# tube_clock_shield_v1.net
KiCad netlist of a schematic drawn in EAGLE
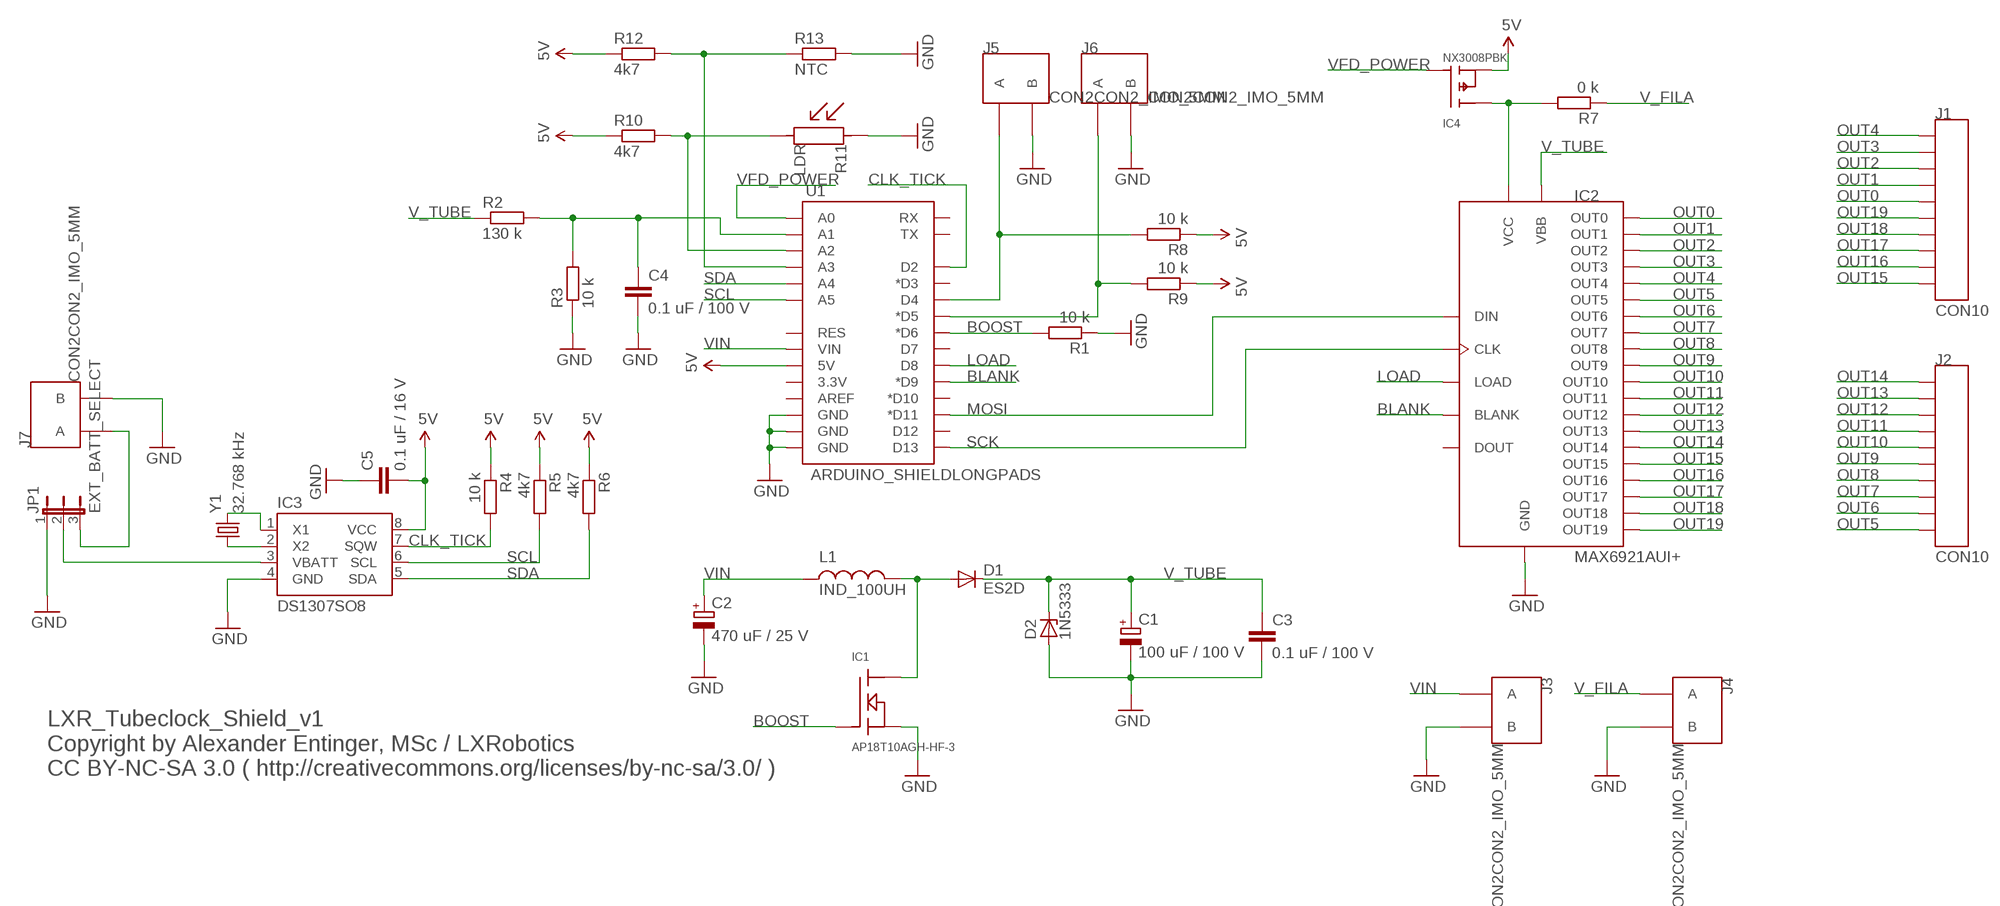
[diagram p0: schematic, sheet 1]

(export (version "E")
  (design (tool "Eeschema 10.0.6"))
  (components
    (comp (ref "C1")
      (value "100 uF / 100 V")
      (footprint "eagle-import:E5-10,5")
      (libsource (lib "eagle-import") (part "CPOL-EUE5-10.5"))
    )
    (comp (ref "C2")
      (value "470 uF / 25 V")
      (footprint "eagle-import:E5-10,5")
      (libsource (lib "eagle-import") (part "CPOL-EUE5-10.5"))
    )
    (comp (ref "C3")
      (value "0.1 uF / 100 V")
      (footprint "eagle-import:C0805")
      (libsource (lib "eagle-import") (part "C-EUC0805"))
    )
    (comp (ref "C4")
      (value "0.1 uF / 100 V")
      (footprint "eagle-import:C0805")
      (libsource (lib "eagle-import") (part "C-EUC0805"))
    )
    (comp (ref "C5")
      (value "0.1 uF / 16 V")
      (footprint "eagle-import:C0805")
      (libsource (lib "eagle-import") (part "C-EUC0805"))
    )
    (comp (ref "D1")
      (value "ES2D")
      (footprint "eagle-import:SMB")
      (libsource (lib "eagle-import") (part "ES2D"))
    )
    (comp (ref "D2")
      (value "1N5333")
      (footprint "eagle-import:C1702-15")
      (libsource (lib "eagle-import") (part "1N5333"))
    )
    (comp (ref "IC1")
      (value "AP18T10AGH-HF-3")
      (footprint "eagle-import:TO252")
      (libsource (lib "eagle-import") (part "AP18T10AGH-HF-3"))
    )
    (comp (ref "IC2")
      (value "MAX6921AUI+")
      (footprint "eagle-import:TSSOP28")
      (libsource (lib "eagle-import") (part "MAX6921AUI+"))
    )
    (comp (ref "IC3")
      (value "DS1307SO8")
      (footprint "eagle-import:SO08")
      (libsource (lib "eagle-import") (part "DS1307SO8"))
    )
    (comp (ref "IC4")
      (value "NX3008PBK")
      (footprint "eagle-import:SOT23")
      (libsource (lib "eagle-import") (part "NX3008PBK"))
    )
    (comp (ref "J1")
      (value "CON10")
      (footprint "eagle-import:CON10")
      (libsource (lib "eagle-import") (part "CON10"))
    )
    (comp (ref "J2")
      (value "CON10")
      (footprint "eagle-import:CON10")
      (libsource (lib "eagle-import") (part "CON10"))
    )
    (comp (ref "J3")
      (value "CON2CON2_IMO_5MM")
      (footprint "eagle-import:CON2_IMO")
      (libsource (lib "eagle-import") (part "CON2CON2_IMO_5MM"))
    )
    (comp (ref "J4")
      (value "CON2CON2_IMO_5MM")
      (footprint "eagle-import:CON2_IMO")
      (libsource (lib "eagle-import") (part "CON2CON2_IMO_5MM"))
    )
    (comp (ref "J5")
      (value "CON2CON2_IMO_5MM")
      (footprint "eagle-import:CON2_IMO")
      (libsource (lib "eagle-import") (part "CON2CON2_IMO_5MM"))
    )
    (comp (ref "J6")
      (value "CON2CON2_IMO_5MM")
      (footprint "eagle-import:CON2_IMO")
      (libsource (lib "eagle-import") (part "CON2CON2_IMO_5MM"))
    )
    (comp (ref "J7")
      (value "CON2CON2_IMO_5MM")
      (footprint "eagle-import:CON2_IMO")
      (libsource (lib "eagle-import") (part "CON2CON2_IMO_5MM"))
    )
    (comp (ref "JP1")
      (value "EXT_BATT_SELECT")
      (footprint "eagle-import:JP2")
      (libsource (lib "eagle-import") (part "JP2E"))
    )
    (comp (ref "L1")
      (value "IND_100UH")
      (footprint "eagle-import:LEISTUNGS_INDUKTIVITAET_PACKAGE")
      (libsource (lib "eagle-import") (part "IND_100UH"))
    )
    (comp (ref "R1")
      (value "10 k")
      (footprint "eagle-import:R0805")
      (libsource (lib "eagle-import") (part "R-EU_R0805"))
    )
    (comp (ref "R2")
      (value "130 k")
      (footprint "eagle-import:R0805")
      (libsource (lib "eagle-import") (part "R-EU_R0805"))
    )
    (comp (ref "R3")
      (value "10 k")
      (footprint "eagle-import:R0805")
      (libsource (lib "eagle-import") (part "R-EU_R0805"))
    )
    (comp (ref "R4")
      (value "10 k")
      (footprint "eagle-import:R0805")
      (libsource (lib "eagle-import") (part "R-EU_R0805"))
    )
    (comp (ref "R5")
      (value "4k7")
      (footprint "eagle-import:R0805")
      (libsource (lib "eagle-import") (part "R-EU_R0805"))
    )
    (comp (ref "R6")
      (value "4k7")
      (footprint "eagle-import:R0805")
      (libsource (lib "eagle-import") (part "R-EU_R0805"))
    )
    (comp (ref "R7")
      (value "0 k")
      (footprint "eagle-import:R0805")
      (libsource (lib "eagle-import") (part "R-EU_R0805"))
    )
    (comp (ref "R8")
      (value "10 k")
      (footprint "eagle-import:R0805")
      (libsource (lib "eagle-import") (part "R-EU_R0805"))
    )
    (comp (ref "R9")
      (value "10 k")
      (footprint "eagle-import:R0805")
      (libsource (lib "eagle-import") (part "R-EU_R0805"))
    )
    (comp (ref "R10")
      (value "4k7")
      (footprint "eagle-import:R0805")
      (libsource (lib "eagle-import") (part "R-EU_R0805"))
    )
    (comp (ref "R11")
      (value "LDR")
      (footprint "eagle-import:LDR")
      (libsource (lib "eagle-import") (part "LDR"))
    )
    (comp (ref "R12")
      (value "4k7")
      (footprint "eagle-import:R0805")
      (libsource (lib "eagle-import") (part "R-EU_R0805"))
    )
    (comp (ref "R13")
      (value "NTC")
      (footprint "eagle-import:R0805")
      (libsource (lib "eagle-import") (part "R-EU_R0805"))
    )
    (comp (ref "U1")
      (value "ARDUINO_SHIELDLONGPADS")
      (footprint "eagle-import:DUEMILANOVE_SHIELD_LONGPADS")
      (libsource (lib "eagle-import") (part "ARDUINO_SHIELDLONGPADS"))
    )
    (comp (ref "Y1")
      (value "32.768 kHz")
      (footprint "eagle-import:TC26HEZ")
      (libsource (lib "eagle-import") (part "CRYSTALTC26H_EZ"))
    )
  )
  (nets
    (net (code "1") (name "/BLANK") (class "Default")
      (node (ref "IC2") (pin "20") (pinfunction "BLANK_20") (pintype "bidirectional"))
      (node (ref "U1") (pin "D9") (pinfunction "*D9_D9") (pintype "bidirectional"))
    )
    (net (code "2") (name "/BOOST") (class "Default")
      (node (ref "IC1") (pin "G") (pinfunction "G_G") (pintype "bidirectional"))
      (node (ref "R1") (pin "2") (pinfunction "2_2") (pintype "passive"))
      (node (ref "U1") (pin "D6") (pinfunction "*D6_D6") (pintype "bidirectional"))
    )
    (net (code "3") (name "/CLK_TICK") (class "Default")
      (node (ref "IC3") (pin "7") (pinfunction "SQW_7") (pintype "bidirectional"))
      (node (ref "R4") (pin "2") (pinfunction "2_2") (pintype "passive"))
      (node (ref "U1") (pin "D2") (pinfunction "D2_D2") (pintype "bidirectional"))
    )
    (net (code "4") (name "/LOAD") (class "Default")
      (node (ref "IC2") (pin "23") (pinfunction "LOAD_23") (pintype "bidirectional"))
      (node (ref "U1") (pin "D8") (pinfunction "D8_D8") (pintype "bidirectional"))
    )
    (net (code "5") (name "/MOSI") (class "Default")
      (node (ref "IC2") (pin "6") (pinfunction "DIN_6") (pintype "bidirectional"))
      (node (ref "U1") (pin "D11") (pinfunction "*D11_D11") (pintype "bidirectional"))
    )
    (net (code "6") (name "/OUT0") (class "Default")
      (node (ref "IC2") (pin "5") (pinfunction "OUT0_5") (pintype "bidirectional"))
      (node (ref "J1") (pin "P$5") (pinfunction "P$5_P$5") (pintype "bidirectional"))
    )
    (net (code "7") (name "/OUT1") (class "Default")
      (node (ref "IC2") (pin "4") (pinfunction "OUT1_4") (pintype "bidirectional"))
      (node (ref "J1") (pin "P$4") (pinfunction "P$4_P$4") (pintype "bidirectional"))
    )
    (net (code "8") (name "/OUT2") (class "Default")
      (node (ref "IC2") (pin "3") (pinfunction "OUT2_3") (pintype "bidirectional"))
      (node (ref "J1") (pin "P$3") (pinfunction "P$3_P$3") (pintype "bidirectional"))
    )
    (net (code "9") (name "/OUT3") (class "Default")
      (node (ref "IC2") (pin "2") (pinfunction "OUT3_2") (pintype "bidirectional"))
      (node (ref "J1") (pin "P$2") (pinfunction "P$2_P$2") (pintype "bidirectional"))
    )
    (net (code "10") (name "/OUT4") (class "Default")
      (node (ref "IC2") (pin "1") (pinfunction "OUT4_1") (pintype "bidirectional"))
      (node (ref "J1") (pin "P$1") (pinfunction "P$1_P$1") (pintype "bidirectional"))
    )
    (net (code "11") (name "/OUT5") (class "Default")
      (node (ref "IC2") (pin "28") (pinfunction "OUT5_28") (pintype "bidirectional"))
      (node (ref "J2") (pin "P$10") (pinfunction "P$10_P$10") (pintype "bidirectional"))
    )
    (net (code "12") (name "/OUT6") (class "Default")
      (node (ref "IC2") (pin "27") (pinfunction "OUT6_27") (pintype "bidirectional"))
      (node (ref "J2") (pin "P$9") (pinfunction "P$9_P$9") (pintype "bidirectional"))
    )
    (net (code "13") (name "/OUT7") (class "Default")
      (node (ref "IC2") (pin "26") (pinfunction "OUT7_26") (pintype "bidirectional"))
      (node (ref "J2") (pin "P$8") (pinfunction "P$8_P$8") (pintype "bidirectional"))
    )
    (net (code "14") (name "/OUT8") (class "Default")
      (node (ref "IC2") (pin "25") (pinfunction "OUT8_25") (pintype "bidirectional"))
      (node (ref "J2") (pin "P$7") (pinfunction "P$7_P$7") (pintype "bidirectional"))
    )
    (net (code "15") (name "/OUT9") (class "Default")
      (node (ref "IC2") (pin "24") (pinfunction "OUT9_24") (pintype "bidirectional"))
      (node (ref "J2") (pin "P$6") (pinfunction "P$6_P$6") (pintype "bidirectional"))
    )
    (net (code "16") (name "/OUT10") (class "Default")
      (node (ref "IC2") (pin "19") (pinfunction "OUT10_19") (pintype "bidirectional"))
      (node (ref "J2") (pin "P$5") (pinfunction "P$5_P$5") (pintype "bidirectional"))
    )
    (net (code "17") (name "/OUT11") (class "Default")
      (node (ref "IC2") (pin "18") (pinfunction "OUT11_18") (pintype "bidirectional"))
      (node (ref "J2") (pin "P$4") (pinfunction "P$4_P$4") (pintype "bidirectional"))
    )
    (net (code "18") (name "/OUT12") (class "Default")
      (node (ref "IC2") (pin "17") (pinfunction "OUT12_17") (pintype "bidirectional"))
      (node (ref "J2") (pin "P$3") (pinfunction "P$3_P$3") (pintype "bidirectional"))
    )
    (net (code "19") (name "/OUT13") (class "Default")
      (node (ref "IC2") (pin "16") (pinfunction "OUT13_16") (pintype "bidirectional"))
      (node (ref "J2") (pin "P$2") (pinfunction "P$2_P$2") (pintype "bidirectional"))
    )
    (net (code "20") (name "/OUT14") (class "Default")
      (node (ref "IC2") (pin "15") (pinfunction "OUT14_15") (pintype "bidirectional"))
      (node (ref "J2") (pin "P$1") (pinfunction "P$1_P$1") (pintype "bidirectional"))
    )
    (net (code "21") (name "/OUT15") (class "Default")
      (node (ref "IC2") (pin "14") (pinfunction "OUT15_14") (pintype "bidirectional"))
      (node (ref "J1") (pin "P$10") (pinfunction "P$10_P$10") (pintype "bidirectional"))
    )
    (net (code "22") (name "/OUT16") (class "Default")
      (node (ref "IC2") (pin "13") (pinfunction "OUT16_13") (pintype "bidirectional"))
      (node (ref "J1") (pin "P$9") (pinfunction "P$9_P$9") (pintype "bidirectional"))
    )
    (net (code "23") (name "/OUT17") (class "Default")
      (node (ref "IC2") (pin "12") (pinfunction "OUT17_12") (pintype "bidirectional"))
      (node (ref "J1") (pin "P$8") (pinfunction "P$8_P$8") (pintype "bidirectional"))
    )
    (net (code "24") (name "/OUT18") (class "Default")
      (node (ref "IC2") (pin "11") (pinfunction "OUT18_11") (pintype "bidirectional"))
      (node (ref "J1") (pin "P$7") (pinfunction "P$7_P$7") (pintype "bidirectional"))
    )
    (net (code "25") (name "/OUT19") (class "Default")
      (node (ref "IC2") (pin "10") (pinfunction "OUT19_10") (pintype "bidirectional"))
      (node (ref "J1") (pin "P$6") (pinfunction "P$6_P$6") (pintype "bidirectional"))
    )
    (net (code "26") (name "/SCK") (class "Default")
      (node (ref "IC2") (pin "22") (pinfunction "CLK_22") (pintype "bidirectional"))
      (node (ref "U1") (pin "D13") (pinfunction "D13_D13") (pintype "bidirectional"))
    )
    (net (code "27") (name "/SCL") (class "Default")
      (node (ref "IC3") (pin "6") (pinfunction "SCL_6") (pintype "bidirectional"))
      (node (ref "R5") (pin "2") (pinfunction "2_2") (pintype "passive"))
      (node (ref "U1") (pin "A5") (pinfunction "A5_A5") (pintype "bidirectional"))
    )
    (net (code "28") (name "/SDA") (class "Default")
      (node (ref "IC3") (pin "5") (pinfunction "SDA_5") (pintype "bidirectional"))
      (node (ref "R6") (pin "2") (pinfunction "2_2") (pintype "passive"))
      (node (ref "U1") (pin "A4") (pinfunction "A4_A4") (pintype "bidirectional"))
    )
    (net (code "29") (name "/VFD_POWER") (class "Default")
      (node (ref "IC4") (pin "1") (pinfunction "G_1") (pintype "bidirectional"))
      (node (ref "U1") (pin "A0") (pinfunction "A0_A0") (pintype "bidirectional"))
    )
    (net (code "30") (name "/VIN") (class "Default")
      (node (ref "C2") (pin "+") (pinfunction "+_+") (pintype "passive"))
      (node (ref "J3") (pin "P$1") (pinfunction "A_P$1") (pintype "bidirectional"))
      (node (ref "L1") (pin "P$1") (pinfunction "P$1_P$1") (pintype "bidirectional"))
      (node (ref "U1") (pin "VIN") (pinfunction "VIN_VIN") (pintype "bidirectional"))
    )
    (net (code "31") (name "/V_FILA") (class "Default")
      (node (ref "J4") (pin "P$1") (pinfunction "A_P$1") (pintype "bidirectional"))
      (node (ref "R7") (pin "1") (pinfunction "1_1") (pintype "passive"))
    )
    (net (code "32") (name "/V_TUBE") (class "Default")
      (node (ref "C1") (pin "+") (pinfunction "+_+") (pintype "passive"))
      (node (ref "C3") (pin "1") (pinfunction "1_1") (pintype "passive"))
      (node (ref "D1") (pin "C") (pinfunction "C_C") (pintype "passive"))
      (node (ref "D2") (pin "C") (pinfunction "C_C") (pintype "passive"))
      (node (ref "IC2") (pin "8") (pinfunction "VBB_8") (pintype "bidirectional"))
      (node (ref "R2") (pin "1") (pinfunction "1_1") (pintype "passive"))
    )
    (net (code "33") (name "5V") (class "Default")
      (node (ref "C5") (pin "2") (pinfunction "2_2") (pintype "passive"))
      (node (ref "IC3") (pin "8") (pinfunction "VCC_8") (pintype "bidirectional"))
      (node (ref "IC4") (pin "2") (pinfunction "S_2") (pintype "bidirectional"))
      (node (ref "R10") (pin "1") (pinfunction "1_1") (pintype "passive"))
      (node (ref "R12") (pin "1") (pinfunction "1_1") (pintype "passive"))
      (node (ref "R4") (pin "1") (pinfunction "1_1") (pintype "passive"))
      (node (ref "R5") (pin "1") (pinfunction "1_1") (pintype "passive"))
      (node (ref "R6") (pin "1") (pinfunction "1_1") (pintype "passive"))
      (node (ref "R8") (pin "1") (pinfunction "1_1") (pintype "passive"))
      (node (ref "R9") (pin "1") (pinfunction "1_1") (pintype "passive"))
      (node (ref "U1") (pin "5V") (pinfunction "5V_5V") (pintype "bidirectional"))
    )
    (net (code "34") (name "GND") (class "Default")
      (node (ref "C1") (pin "-") (pinfunction "-_-") (pintype "passive"))
      (node (ref "C2") (pin "-") (pinfunction "-_-") (pintype "passive"))
      (node (ref "C3") (pin "2") (pinfunction "2_2") (pintype "passive"))
      (node (ref "C4") (pin "2") (pinfunction "2_2") (pintype "passive"))
      (node (ref "C5") (pin "1") (pinfunction "1_1") (pintype "passive"))
      (node (ref "D2") (pin "A") (pinfunction "A_A") (pintype "passive"))
      (node (ref "IC1") (pin "S") (pinfunction "S_S") (pintype "bidirectional"))
      (node (ref "IC2") (pin "21") (pinfunction "GND_21") (pintype "bidirectional"))
      (node (ref "IC3") (pin "4") (pinfunction "GND_4") (pintype "bidirectional"))
      (node (ref "J3") (pin "P$2") (pinfunction "B_P$2") (pintype "bidirectional"))
      (node (ref "J4") (pin "P$2") (pinfunction "B_P$2") (pintype "bidirectional"))
      (node (ref "J5") (pin "P$2") (pinfunction "B_P$2") (pintype "bidirectional"))
      (node (ref "J6") (pin "P$2") (pinfunction "B_P$2") (pintype "bidirectional"))
      (node (ref "J7") (pin "P$2") (pinfunction "B_P$2") (pintype "bidirectional"))
      (node (ref "JP1") (pin "1") (pinfunction "1_1") (pintype "passive"))
      (node (ref "R1") (pin "1") (pinfunction "1_1") (pintype "passive"))
      (node (ref "R11") (pin "P$1") (pinfunction "P$1_P$1") (pintype "bidirectional"))
      (node (ref "R13") (pin "2") (pinfunction "2_2") (pintype "passive"))
      (node (ref "R3") (pin "1") (pinfunction "1_1") (pintype "passive"))
      (node (ref "U1") (pin "GND@0") (pinfunction "GND_GND@0") (pintype "bidirectional"))
      (node (ref "U1") (pin "GND@1") (pinfunction "GND_GND@1") (pintype "bidirectional"))
      (node (ref "U1") (pin "GND@2") (pinfunction "GND_GND@2") (pintype "bidirectional"))
    )
    (net (code "35") (name "Net-(C4-Pad1)") (class "Default")
      (node (ref "C4") (pin "1") (pinfunction "1_1") (pintype "passive"))
      (node (ref "R2") (pin "2") (pinfunction "2_2") (pintype "passive"))
      (node (ref "R3") (pin "2") (pinfunction "2_2") (pintype "passive"))
      (node (ref "U1") (pin "A1") (pinfunction "A1_A1") (pintype "bidirectional"))
    )
    (net (code "36") (name "Net-(D1-PadA)") (class "Default")
      (node (ref "D1") (pin "A") (pinfunction "A_A") (pintype "passive"))
      (node (ref "IC1") (pin "D") (pinfunction "D_D") (pintype "bidirectional"))
      (node (ref "L1") (pin "P$2") (pinfunction "P$2_P$2") (pintype "bidirectional"))
    )
    (net (code "37") (name "Net-(IC2-VCC)") (class "Default")
      (node (ref "IC2") (pin "7") (pinfunction "VCC_7") (pintype "bidirectional"))
      (node (ref "IC4") (pin "3") (pinfunction "D_3") (pintype "bidirectional"))
      (node (ref "R7") (pin "2") (pinfunction "2_2") (pintype "passive"))
    )
    (net (code "38") (name "Net-(IC3-VBATT)") (class "Default")
      (node (ref "IC3") (pin "3") (pinfunction "VBATT_3") (pintype "bidirectional"))
      (node (ref "JP1") (pin "2") (pinfunction "2_2") (pintype "passive"))
    )
    (net (code "39") (name "Net-(IC3-X1)") (class "Default")
      (node (ref "IC3") (pin "1") (pinfunction "X1_1") (pintype "bidirectional"))
      (node (ref "Y1") (pin "2") (pinfunction "2_2") (pintype "passive"))
    )
    (net (code "40") (name "Net-(IC3-X2)") (class "Default")
      (node (ref "IC3") (pin "2") (pinfunction "X2_2") (pintype "bidirectional"))
      (node (ref "Y1") (pin "1") (pinfunction "1_1") (pintype "passive"))
    )
    (net (code "41") (name "Net-(J5-A)") (class "Default")
      (node (ref "J5") (pin "P$1") (pinfunction "A_P$1") (pintype "bidirectional"))
      (node (ref "R8") (pin "2") (pinfunction "2_2") (pintype "passive"))
      (node (ref "U1") (pin "D4") (pinfunction "D4_D4") (pintype "bidirectional"))
    )
    (net (code "42") (name "Net-(J6-A)") (class "Default")
      (node (ref "J6") (pin "P$1") (pinfunction "A_P$1") (pintype "bidirectional"))
      (node (ref "R9") (pin "2") (pinfunction "2_2") (pintype "passive"))
      (node (ref "U1") (pin "D5") (pinfunction "*D5_D5") (pintype "bidirectional"))
    )
    (net (code "43") (name "Net-(J7-A)") (class "Default")
      (node (ref "J7") (pin "P$1") (pinfunction "A_P$1") (pintype "bidirectional"))
      (node (ref "JP1") (pin "3") (pinfunction "3_3") (pintype "passive"))
    )
    (net (code "44") (name "Net-(R10-Pad2)") (class "Default")
      (node (ref "R10") (pin "2") (pinfunction "2_2") (pintype "passive"))
      (node (ref "R11") (pin "P$2") (pinfunction "P$2_P$2") (pintype "bidirectional"))
      (node (ref "U1") (pin "A2") (pinfunction "A2_A2") (pintype "bidirectional"))
    )
    (net (code "45") (name "Net-(R12-Pad2)") (class "Default")
      (node (ref "R12") (pin "2") (pinfunction "2_2") (pintype "passive"))
      (node (ref "R13") (pin "1") (pinfunction "1_1") (pintype "passive"))
      (node (ref "U1") (pin "A3") (pinfunction "A3_A3") (pintype "bidirectional"))
    )
    (net (code "46") (name "unconnected-(IC2-DOUT-Pad9)") (class "Default")
      (node (ref "IC2") (pin "9") (pinfunction "DOUT_9") (pintype "bidirectional"))
    )
    (net (code "47") (name "unconnected-(U1-*D3-PadD3)") (class "Default")
      (node (ref "U1") (pin "D3") (pinfunction "*D3_D3") (pintype "bidirectional"))
    )
    (net (code "48") (name "unconnected-(U1-*D10-PadD10)") (class "Default")
      (node (ref "U1") (pin "D10") (pinfunction "*D10_D10") (pintype "bidirectional"))
    )
    (net (code "49") (name "unconnected-(U1-Pad3.3V)") (class "Default")
      (node (ref "U1") (pin "3.3V") (pinfunction "3.3V_3.3V") (pintype "bidirectional"))
    )
    (net (code "50") (name "unconnected-(U1-PadAREF)") (class "Default")
      (node (ref "U1") (pin "AREF") (pinfunction "AREF_AREF") (pintype "bidirectional"))
    )
    (net (code "51") (name "unconnected-(U1-PadD7)") (class "Default")
      (node (ref "U1") (pin "D7") (pinfunction "D7_D7") (pintype "bidirectional"))
    )
    (net (code "52") (name "unconnected-(U1-PadD12)") (class "Default")
      (node (ref "U1") (pin "D12") (pinfunction "D12_D12") (pintype "bidirectional"))
    )
    (net (code "53") (name "unconnected-(U1-PadRES)") (class "Default")
      (node (ref "U1") (pin "RES") (pinfunction "RES_RES") (pintype "bidirectional"))
    )
    (net (code "54") (name "unconnected-(U1-PadRX)") (class "Default")
      (node (ref "U1") (pin "RX") (pinfunction "RX_RX") (pintype "bidirectional"))
    )
    (net (code "55") (name "unconnected-(U1-PadTX)") (class "Default")
      (node (ref "U1") (pin "TX") (pinfunction "TX_TX") (pintype "bidirectional"))
    )
  )
)
